# Schematic_2023-01-06.net
KiCad netlist of a schematic drawn in Altium Designer
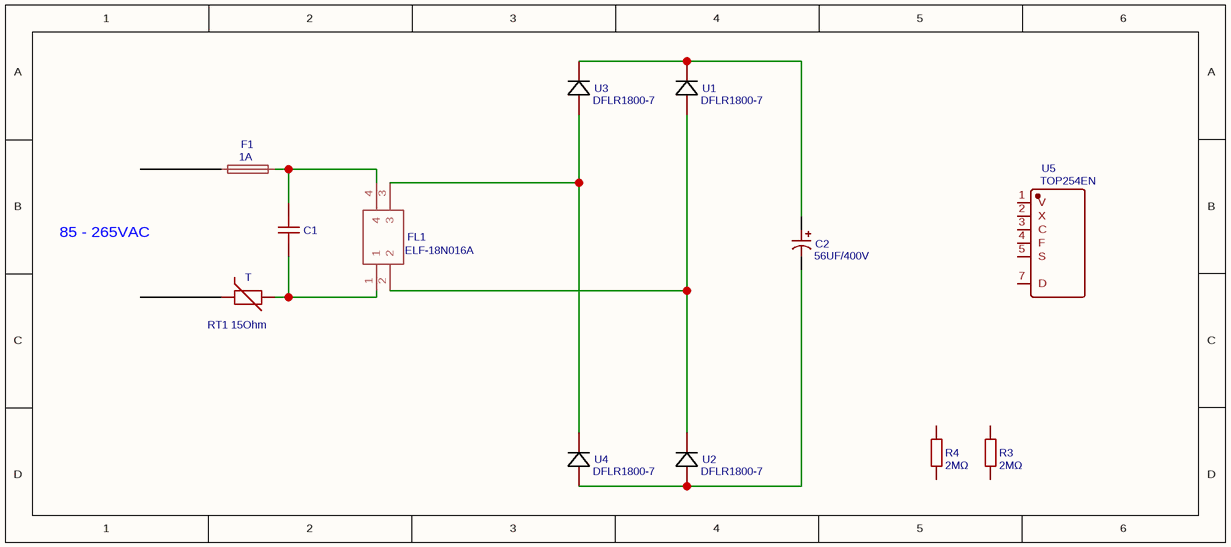
[diagram p0: Schematic_2023-01-06.schdoc]

(export (version "E")
  (design (tool "Eeschema 10.0.6"))
  (components
    (comp (ref "C1")
      (value "C212G473K3AC000")
      (fields (field (name "BOM_SUPPLIER PART") "C3025105") (field (name "CONTRIBUTOR") "lcsc"))
      (libsource (lib "altium-import") (part "root_1_C212G473K3AC000_"))
    )
    (comp (ref "C2")
      (value "56UF/400V")
      (fields
        (field (name "BOM_SUPPLIER PART") "C9900023263")
        (field (name "BOM_MANUFACTURER PART") "47uF/400V")
        (field (name "CONTRIBUTOR") "lcsc")
      )
      (libsource (lib "altium-import") (part "root_3_56UF/400V_"))
    )
    (comp (ref "F1")
      (value "1A")
      (fields (field (name "CONTRIBUTOR") "icet-t1"))
      (libsource (lib "altium-import") (part "root_0_1A_"))
    )
    (comp (ref "FL1")
      (value "ELF-18N016A")
      (fields (field (name "CONTRIBUTOR") "Praudyogi_EE"))
      (libsource (lib "altium-import") (part "root_1_ELF-18N016A_"))
    )
    (comp (ref "R3")
      (value "2MΩ")
      (fields
        (field (name "BOM_SUPPLIER PART") "C116786")
        (field (name "BOM_MANUFACTURER PART") "MHR0314SA207F70")
        (field (name "CONTRIBUTOR") "LCSC")
      )
      (libsource (lib "altium-import") (part "root_1_2MΩ_"))
    )
    (comp (ref "R4")
      (value "2MΩ")
      (fields
        (field (name "BOM_SUPPLIER PART") "C116786")
        (field (name "BOM_MANUFACTURER PART") "MHR0314SA207F70")
        (field (name "CONTRIBUTOR") "LCSC")
      )
      (libsource (lib "altium-import") (part "root_1_2MΩ_"))
    )
    (comp (ref "T")
      (value "RT1 15Ohm")
      (fields (field (name "CONTRIBUTOR") "dentflexbrasil"))
      (libsource (lib "altium-import") (part "root_3_RT1 15Ohm_"))
    )
    (comp (ref "U1")
      (value "DFLR1800-7")
      (fields (field (name "CONTRIBUTOR") "nscw2011"))
      (libsource (lib "altium-import") (part "root_3_DFLR1800-7_"))
    )
    (comp (ref "U2")
      (value "DFLR1800-7")
      (fields (field (name "CONTRIBUTOR") "nscw2011"))
      (libsource (lib "altium-import") (part "root_3_DFLR1800-7_"))
    )
    (comp (ref "U3")
      (value "DFLR1800-7")
      (fields (field (name "CONTRIBUTOR") "nscw2011"))
      (libsource (lib "altium-import") (part "root_3_DFLR1800-7_"))
    )
    (comp (ref "U4")
      (value "DFLR1800-7")
      (fields (field (name "CONTRIBUTOR") "nscw2011"))
      (libsource (lib "altium-import") (part "root_3_DFLR1800-7_"))
    )
    (comp (ref "U5")
      (value "TOP254EN")
      (fields (field (name "BOM_SUPPLIER PART") "C568146") (field (name "CONTRIBUTOR") "lcsc"))
      (libsource (lib "altium-import") (part "root_0_TOP254EN_"))
    )
  )
  (nets
    (net (code "1") (name "Net-(C1-Pad1)") (class "Default")
      (node (ref "C1") (pin "1") (pinfunction "1_1") (pintype "passive"))
      (node (ref "FL1") (pin "1") (pinfunction "1_1") (pintype "passive"))
      (node (ref "T") (pin "1") (pinfunction "1_1") (pintype "passive"))
    )
    (net (code "2") (name "Net-(C1-Pad2)") (class "Default")
      (node (ref "C1") (pin "2") (pinfunction "2_2") (pintype "passive"))
      (node (ref "F1") (pin "2") (pinfunction "2_2") (pintype "passive"))
      (node (ref "FL1") (pin "4") (pinfunction "4_4") (pintype "passive"))
    )
    (net (code "3") (name "Net-(C2-Pad1)") (class "Default")
      (node (ref "C2") (pin "1") (pinfunction "1_1") (pintype "passive"))
      (node (ref "U1") (pin "2") (pinfunction "2_2") (pintype "passive"))
      (node (ref "U3") (pin "2") (pinfunction "2_2") (pintype "passive"))
    )
    (net (code "4") (name "Net-(C2-Pad2)") (class "Default")
      (node (ref "C2") (pin "2") (pinfunction "2_2") (pintype "passive"))
      (node (ref "U2") (pin "1") (pinfunction "1_1") (pintype "passive"))
      (node (ref "U4") (pin "1") (pinfunction "1_1") (pintype "passive"))
    )
    (net (code "5") (name "Net-(FL1-Pad2)") (class "Default")
      (node (ref "FL1") (pin "2") (pinfunction "2_2") (pintype "passive"))
      (node (ref "U1") (pin "1") (pinfunction "1_1") (pintype "passive"))
      (node (ref "U2") (pin "2") (pinfunction "2_2") (pintype "passive"))
    )
    (net (code "6") (name "Net-(FL1-Pad3)") (class "Default")
      (node (ref "FL1") (pin "3") (pinfunction "3_3") (pintype "passive"))
      (node (ref "U3") (pin "1") (pinfunction "1_1") (pintype "passive"))
      (node (ref "U4") (pin "2") (pinfunction "2_2") (pintype "passive"))
    )
    (net (code "7") (name "unconnected-(F1-Pad1)") (class "Default")
      (node (ref "F1") (pin "1") (pinfunction "1_1") (pintype "passive"))
    )
    (net (code "8") (name "unconnected-(R3-Pad1)") (class "Default")
      (node (ref "R3") (pin "1") (pinfunction "1_1") (pintype "passive"))
    )
    (net (code "9") (name "unconnected-(R3-Pad2)") (class "Default")
      (node (ref "R3") (pin "2") (pinfunction "2_2") (pintype "passive"))
    )
    (net (code "10") (name "unconnected-(R4-Pad1)") (class "Default")
      (node (ref "R4") (pin "1") (pinfunction "1_1") (pintype "passive"))
    )
    (net (code "11") (name "unconnected-(R4-Pad2)") (class "Default")
      (node (ref "R4") (pin "2") (pinfunction "2_2") (pintype "passive"))
    )
    (net (code "12") (name "unconnected-(T-Pad2)") (class "Default")
      (node (ref "T") (pin "2") (pinfunction "2_2") (pintype "passive"))
    )
    (net (code "13") (name "unconnected-(U5-C-Pad3)") (class "Default")
      (node (ref "U5") (pin "3") (pinfunction "C_3") (pintype "passive"))
    )
    (net (code "14") (name "unconnected-(U5-D-Pad7)") (class "Default")
      (node (ref "U5") (pin "7") (pinfunction "D_7") (pintype "passive"))
    )
    (net (code "15") (name "unconnected-(U5-F-Pad4)") (class "Default")
      (node (ref "U5") (pin "4") (pinfunction "F_4") (pintype "passive"))
    )
    (net (code "16") (name "unconnected-(U5-S-Pad5)") (class "Default")
      (node (ref "U5") (pin "5") (pinfunction "S_5") (pintype "passive"))
    )
    (net (code "17") (name "unconnected-(U5-V-Pad1)") (class "Default")
      (node (ref "U5") (pin "1") (pinfunction "V_1") (pintype "passive"))
    )
    (net (code "18") (name "unconnected-(U5-X-Pad2)") (class "Default")
      (node (ref "U5") (pin "2") (pinfunction "X_2") (pintype "passive"))
    )
  )
)
